# 9v5_schem.net
KiCad netlist of a schematic drawn in Altium Designer
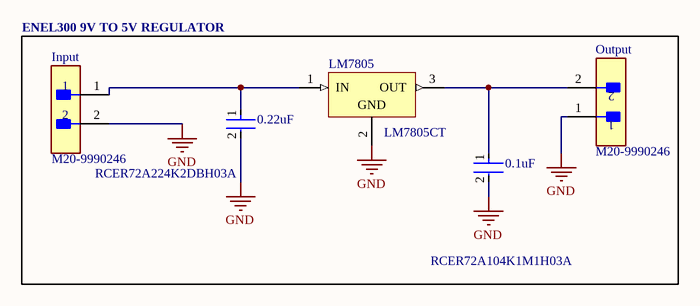
[diagram p0: 9v5_schem.SchDoc]

(export (version "E")
  (design (tool "Eeschema 10.0.6"))
  (components
    (comp (ref "0.1uF")
      (value "RCER72A104K1M1H03A")
      (footprint "FP-RCE1K1-2_5-MFG")
      (description "Cap Ceramic Monolithic 100nF 100V 10% Thru-Hole Bulk")
      (fields (field (name "TOLERANCE") "10%"))
      (libsource (lib "Altium Content Vault") (part "02cd4be3c70576c341d710602a673aa"))
    )
    (comp (ref "0.22uF")
      (value "RCER72A224K2DBH03A")
      (footprint "FP-RCE2A2-MFG")
      (description "Cap Ceramic 220nF 100V X7R ±10% Radial 2.5mm +125°C Automotive Ammo Pack")
      (fields (field (name "TOLERANCE") "10%"))
      (libsource (lib "Altium Content Vault") (part "b4654b650e69147ec39a6b967a45e02"))
    )
    (comp (ref "Input")
      (value "M20-9990246")
      (footprint "FP-M20-9990246-MFG")
      (description "CONN HEADER VERT 2POS 2.54MM")
      (fields
        (field (name "OCTOPART") "https://octopart.com/m20-9990246-harwin-2590635")
        (field (name "MANUFACTURER") "Harwin")
      )
      (libsource (lib "") (part "3bc925449376181038e59eaffc5286c_1"))
    )
    (comp (ref "LM7805")
      (value "LM7805CT")
      (footprint "FAIR-TO-220-3")
      (description "Positive Voltage Regulator, 5 V, 1 A, -40 to 125 degC, 3-Pin TO-220, RoHS, Tube")
      (fields (field (name "MANUFACTURER") "FairchildSemiconductor"))
      (libsource (lib "Altium Content Vault") (part "FAIR-LM7805CT-TO220-3"))
    )
    (comp (ref "Output")
      (value "M20-9990246")
      (footprint "FP-M20-9990246-MFG")
      (description "CONN HEADER VERT 2POS 2.54MM")
      (fields
        (field (name "OCTOPART") "https://octopart.com/m20-9990246-harwin-2590635")
        (field (name "MANUFACTURER") "Harwin")
      )
      (libsource (lib "Altium Content Vault") (part "3bc925449376181038e59eaffc5286c"))
    )
  )
  (nets
    (net (code "1") (name "GND") (class "Default")
      (node (ref "0.1uF") (pin "2") (pinfunction "2_2") (pintype "passive"))
      (node (ref "0.22uF") (pin "2") (pinfunction "2_2") (pintype "passive"))
      (node (ref "Input") (pin "2") (pinfunction "2_2") (pintype "passive"))
      (node (ref "LM7805") (pin "2") (pinfunction "GND_2") (pintype "power_in"))
      (node (ref "Output") (pin "1") (pinfunction "1_1") (pintype "passive"))
    )
    (net (code "2") (name "Net-(LM7805-IN)") (class "Default")
      (node (ref "0.22uF") (pin "1") (pinfunction "1_1") (pintype "passive"))
      (node (ref "Input") (pin "1") (pinfunction "1_1") (pintype "passive"))
      (node (ref "LM7805") (pin "1") (pinfunction "IN_1") (pintype "input"))
    )
    (net (code "3") (name "Net-(LM7805-OUT)") (class "Default")
      (node (ref "0.1uF") (pin "1") (pinfunction "1_1") (pintype "passive"))
      (node (ref "LM7805") (pin "3") (pinfunction "OUT_3") (pintype "output"))
      (node (ref "Output") (pin "2") (pinfunction "2_2") (pintype "passive"))
    )
  )
)
